# PCB_MAIN.net
KiCad netlist of a schematic drawn in EAGLE
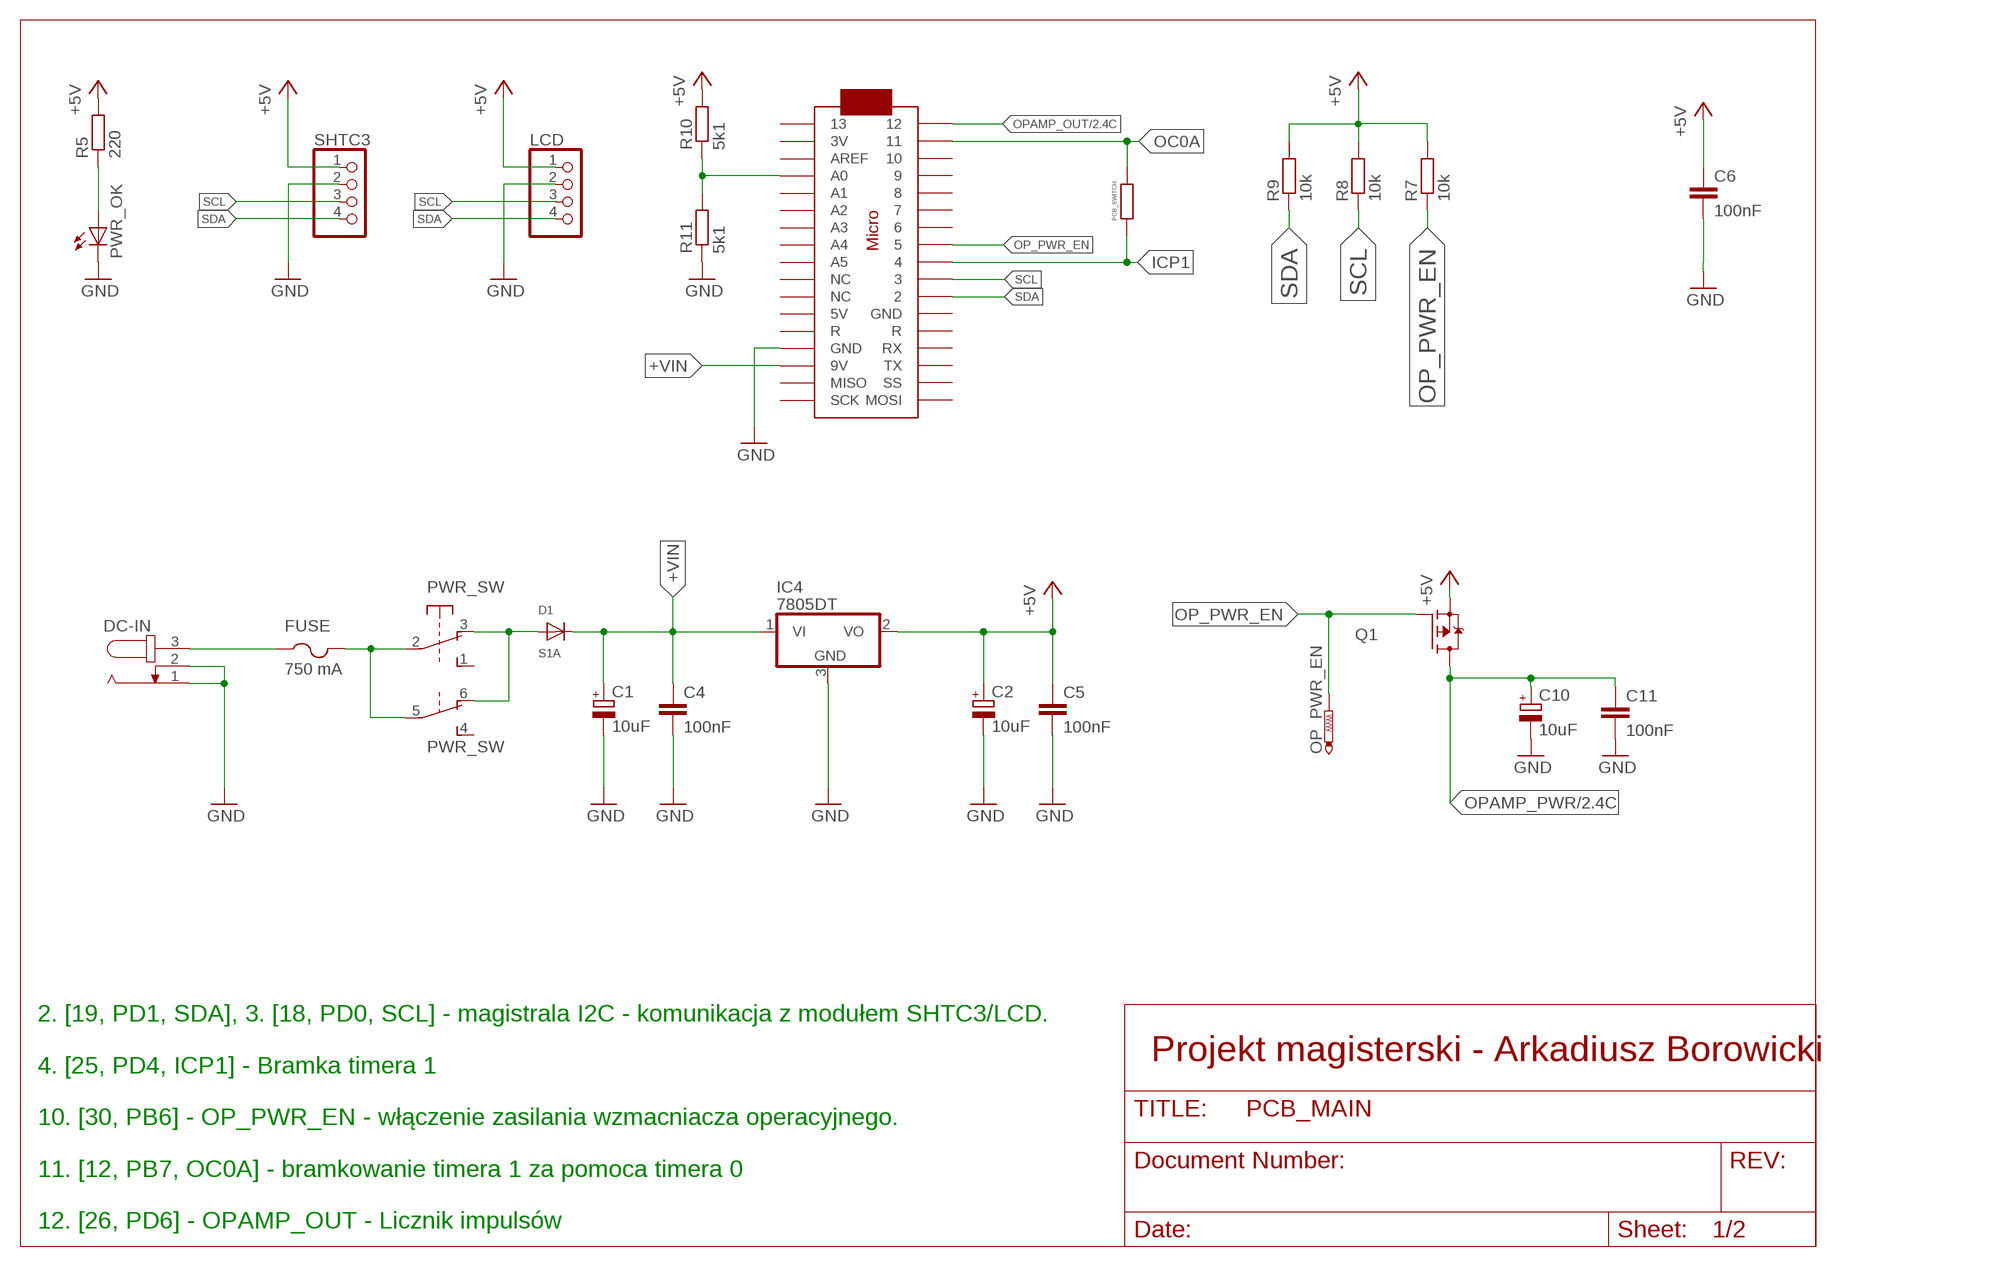
[diagram p0: schematic, sheet 1]
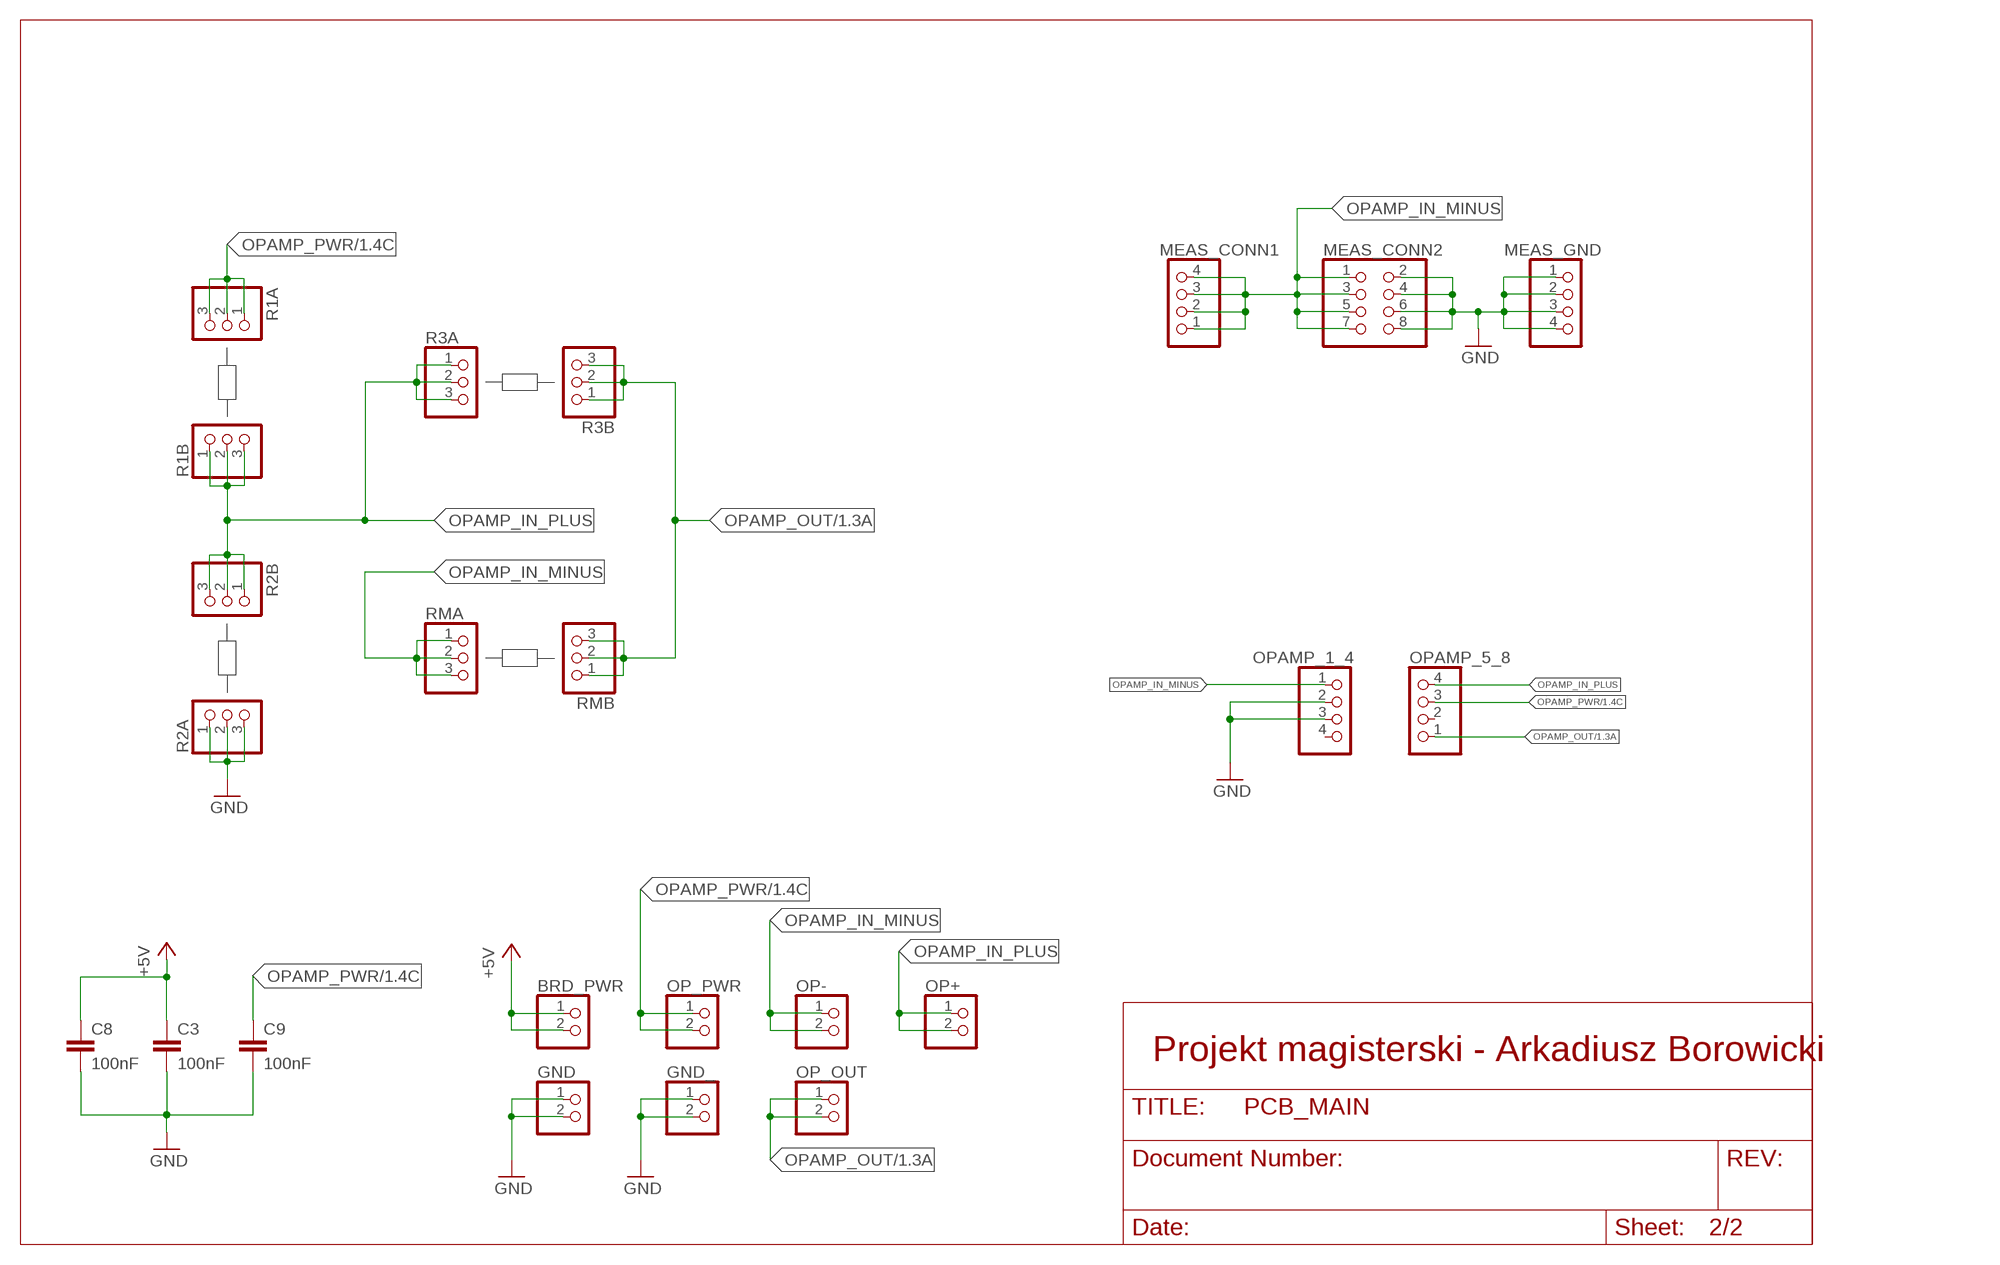
[diagram p1: schematic, sheet 2]

(export (version "E")
  (design (tool "Eeschema 10.0.6"))
  (components
    (comp (ref "BRD_PWR")
      (value "PINHD-1X2")
      (footprint "eagle-import:1X02")
      (libsource (lib "eagle-import") (part "PINHD-1X2"))
    )
    (comp (ref "C3")
      (value "100nF")
      (footprint "eagle-import:C1206K")
      (libsource (lib "eagle-import") (part "C-EUC1206K"))
    )
    (comp (ref "C8")
      (value "100nF")
      (footprint "eagle-import:C1206K")
      (libsource (lib "eagle-import") (part "C-EUC1206K"))
    )
    (comp (ref "C9")
      (value "100nF")
      (footprint "eagle-import:C1206K")
      (libsource (lib "eagle-import") (part "C-EUC1206K"))
    )
    (comp (ref "GND")
      (value "PINHD-1X2")
      (footprint "eagle-import:1X02")
      (libsource (lib "eagle-import") (part "PINHD-1X2"))
    )
    (comp (ref "GND_")
      (value "PINHD-1X2")
      (footprint "eagle-import:1X02")
      (libsource (lib "eagle-import") (part "PINHD-1X2"))
    )
    (comp (ref "MEAS_CONN1")
      (value "PINHD-1X4")
      (footprint "eagle-import:1X04")
      (libsource (lib "eagle-import") (part "PINHD-1X4"))
    )
    (comp (ref "MEAS_CONN2")
      (value "PINHD-2X4")
      (footprint "eagle-import:2X04")
      (libsource (lib "eagle-import") (part "PINHD-2X4"))
    )
    (comp (ref "MEAS_GND")
      (value "PINHD-1X4")
      (footprint "eagle-import:1X04")
      (libsource (lib "eagle-import") (part "PINHD-1X4"))
    )
    (comp (ref "OP+")
      (value "PINHD-1X2")
      (footprint "eagle-import:1X02")
      (libsource (lib "eagle-import") (part "PINHD-1X2"))
    )
    (comp (ref "OP-")
      (value "PINHD-1X2")
      (footprint "eagle-import:1X02")
      (libsource (lib "eagle-import") (part "PINHD-1X2"))
    )
    (comp (ref "OPAMP_1_4")
      (value "PINHD-1X4")
      (footprint "eagle-import:1X04")
      (libsource (lib "eagle-import") (part "PINHD-1X4"))
    )
    (comp (ref "OPAMP_5_8")
      (value "PINHD-1X4")
      (footprint "eagle-import:1X04")
      (libsource (lib "eagle-import") (part "PINHD-1X4"))
    )
    (comp (ref "OP_OUT")
      (value "PINHD-1X2")
      (footprint "eagle-import:1X02")
      (libsource (lib "eagle-import") (part "PINHD-1X2"))
    )
    (comp (ref "OP_PWR")
      (value "PINHD-1X2")
      (footprint "eagle-import:1X02")
      (libsource (lib "eagle-import") (part "PINHD-1X2"))
    )
    (comp (ref "R1A")
      (value "PINHD-1X3")
      (footprint "eagle-import:1X03")
      (libsource (lib "eagle-import") (part "PINHD-1X3"))
    )
    (comp (ref "R1B")
      (value "PINHD-1X3")
      (footprint "eagle-import:1X03")
      (libsource (lib "eagle-import") (part "PINHD-1X3"))
    )
    (comp (ref "R2A")
      (value "PINHD-1X3")
      (footprint "eagle-import:1X03")
      (libsource (lib "eagle-import") (part "PINHD-1X3"))
    )
    (comp (ref "R2B")
      (value "PINHD-1X3")
      (footprint "eagle-import:1X03")
      (libsource (lib "eagle-import") (part "PINHD-1X3"))
    )
    (comp (ref "R3A")
      (value "PINHD-1X3")
      (footprint "eagle-import:1X03")
      (libsource (lib "eagle-import") (part "PINHD-1X3"))
    )
    (comp (ref "R3B")
      (value "PINHD-1X3")
      (footprint "eagle-import:1X03")
      (libsource (lib "eagle-import") (part "PINHD-1X3"))
    )
    (comp (ref "RMA")
      (value "PINHD-1X3")
      (footprint "eagle-import:1X03")
      (libsource (lib "eagle-import") (part "PINHD-1X3"))
    )
    (comp (ref "RMB")
      (value "PINHD-1X3")
      (footprint "eagle-import:1X03")
      (libsource (lib "eagle-import") (part "PINHD-1X3"))
    )
    (comp (ref "C1")
      (value "10uF")
      (footprint "eagle-import:153CLV-0605")
      (libsource (lib "eagle-import") (part "CPOL-EU153CLV-0605"))
    )
    (comp (ref "C2")
      (value "10uF")
      (footprint "eagle-import:153CLV-0605")
      (libsource (lib "eagle-import") (part "CPOL-EU153CLV-0605"))
    )
    (comp (ref "C4")
      (value "100nF")
      (footprint "eagle-import:C1206K")
      (libsource (lib "eagle-import") (part "C-EUC1206K"))
    )
    (comp (ref "C5")
      (value "100nF")
      (footprint "eagle-import:C1206K")
      (libsource (lib "eagle-import") (part "C-EUC1206K"))
    )
    (comp (ref "C6")
      (value "100nF")
      (footprint "eagle-import:C1206K")
      (libsource (lib "eagle-import") (part "C-EUC1206K"))
    )
    (comp (ref "C10")
      (value "10uF")
      (footprint "eagle-import:153CLV-0605")
      (libsource (lib "eagle-import") (part "CPOL-EU153CLV-0605"))
    )
    (comp (ref "C11")
      (value "100nF")
      (footprint "eagle-import:C1206K")
      (libsource (lib "eagle-import") (part "C-EUC1206K"))
    )
    (comp (ref "D1")
      (value "S1A")
      (footprint "eagle-import:SMADIODE")
      (libsource (lib "eagle-import") (part "DIODESMA"))
    )
    (comp (ref "DC-IN")
      (value "JACK-PLUG1")
      (footprint "eagle-import:SPC4078")
      (libsource (lib "eagle-import") (part "JACK-PLUG1"))
    )
    (comp (ref "FUSE")
      (value "750 mA")
      (footprint "eagle-import:1812")
      (libsource (lib "eagle-import") (part "PTCFUSE-1812"))
    )
    (comp (ref "IC4")
      (value "7805DT")
      (footprint "eagle-import:TO252")
      (libsource (lib "eagle-import") (part "78DT05"))
    )
    (comp (ref "LCD")
      (value "PINHD-1X4")
      (footprint "eagle-import:1X04")
      (libsource (lib "eagle-import") (part "PINHD-1X4"))
    )
    (comp (ref "OP_PWR_EN")
      (value "PTR1TP20R")
      (footprint "eagle-import:TP20R")
      (libsource (lib "eagle-import") (part "PTR1TP20R"))
    )
    (comp (ref "PCB_SWITCH")
      (value "R-EU_R0402")
      (footprint "eagle-import:R0402")
      (libsource (lib "eagle-import") (part "resistor_348_R-EU_R0402"))
    )
    (comp (ref "PWR_OK")
      (value "LEDSMT1206")
      (footprint "eagle-import:1206")
      (libsource (lib "eagle-import") (part "LEDSMT1206"))
    )
    (comp (ref "PWR_SW")
      (value "9077-2")
      (footprint "eagle-import:9077-2")
      (libsource (lib "eagle-import") (part "9077-2"))
    )
    (comp (ref "Q1")
      (value "SPD30P06PTO252")
      (footprint "eagle-import:TO252")
      (libsource (lib "eagle-import") (part "SPD30P06PTO252"))
    )
    (comp (ref "R5")
      (value "220")
      (footprint "eagle-import:R1206")
      (libsource (lib "eagle-import") (part "R-EU_R1206"))
    )
    (comp (ref "R7")
      (value "10k")
      (footprint "eagle-import:R1206")
      (libsource (lib "eagle-import") (part "R-EU_R1206"))
    )
    (comp (ref "R8")
      (value "10k")
      (footprint "eagle-import:R1206")
      (libsource (lib "eagle-import") (part "R-EU_R1206"))
    )
    (comp (ref "R9")
      (value "10k")
      (footprint "eagle-import:R1206")
      (libsource (lib "eagle-import") (part "R-EU_R1206"))
    )
    (comp (ref "R10")
      (value "5k1")
      (footprint "eagle-import:R1206")
      (libsource (lib "eagle-import") (part "R-EU_R1206"))
    )
    (comp (ref "R11")
      (value "5k1")
      (footprint "eagle-import:R1206")
      (libsource (lib "eagle-import") (part "R-EU_R1206"))
    )
    (comp (ref "SHTC3")
      (value "PINHD-1X4")
      (footprint "eagle-import:1X04")
      (libsource (lib "eagle-import") (part "PINHD-1X4"))
    )
    (comp (ref "U$1")
      (value "ARDUINOMICRO")
      (footprint "eagle-import:ARDUINOMICRO")
      (libsource (lib "eagle-import") (part "ARDUINOMICRO"))
    )
  )
  (nets
    (net (code "1") (name "+5V") (class "Default")
      (node (ref "BRD_PWR") (pin "1") (pinfunction "1_1") (pintype "passive"))
      (node (ref "BRD_PWR") (pin "2") (pinfunction "2_2") (pintype "passive"))
      (node (ref "C2") (pin "+") (pinfunction "+_+") (pintype "passive"))
      (node (ref "C3") (pin "1") (pinfunction "1_1") (pintype "passive"))
      (node (ref "C5") (pin "1") (pinfunction "1_1") (pintype "passive"))
      (node (ref "C6") (pin "1") (pinfunction "1_1") (pintype "passive"))
      (node (ref "C8") (pin "1") (pinfunction "1_1") (pintype "passive"))
      (node (ref "IC4") (pin "2") (pinfunction "VO_2") (pintype "passive"))
      (node (ref "LCD") (pin "1") (pinfunction "1_1") (pintype "passive"))
      (node (ref "Q1") (pin "2") (pinfunction "S_2") (pintype "passive"))
      (node (ref "R10") (pin "2") (pinfunction "2_2") (pintype "passive"))
      (node (ref "R5") (pin "2") (pinfunction "2_2") (pintype "passive"))
      (node (ref "R7") (pin "2") (pinfunction "2_2") (pintype "passive"))
      (node (ref "R8") (pin "2") (pinfunction "2_2") (pintype "passive"))
      (node (ref "R9") (pin "2") (pinfunction "2_2") (pintype "passive"))
      (node (ref "SHTC3") (pin "1") (pinfunction "1_1") (pintype "passive"))
    )
    (net (code "2") (name "+VIN") (class "Default")
      (node (ref "C1") (pin "+") (pinfunction "+_+") (pintype "passive"))
      (node (ref "C4") (pin "1") (pinfunction "1_1") (pintype "passive"))
      (node (ref "D1") (pin "C") (pinfunction "C_C") (pintype "passive"))
      (node (ref "IC4") (pin "1") (pinfunction "VI_1") (pintype "input"))
      (node (ref "U$1") (pin "P$20") (pinfunction "9V_P$20") (pintype "bidirectional"))
    )
    (net (code "3") (name "GND") (class "Default")
      (node (ref "C1") (pin "-") (pinfunction "-_-") (pintype "passive"))
      (node (ref "C10") (pin "-") (pinfunction "-_-") (pintype "passive"))
      (node (ref "C11") (pin "2") (pinfunction "2_2") (pintype "passive"))
      (node (ref "C2") (pin "-") (pinfunction "-_-") (pintype "passive"))
      (node (ref "C3") (pin "2") (pinfunction "2_2") (pintype "passive"))
      (node (ref "C4") (pin "2") (pinfunction "2_2") (pintype "passive"))
      (node (ref "C5") (pin "2") (pinfunction "2_2") (pintype "passive"))
      (node (ref "C6") (pin "2") (pinfunction "2_2") (pintype "passive"))
      (node (ref "C8") (pin "2") (pinfunction "2_2") (pintype "passive"))
      (node (ref "C9") (pin "2") (pinfunction "2_2") (pintype "passive"))
      (node (ref "DC-IN") (pin "1") (pinfunction "1_1") (pintype "passive"))
      (node (ref "DC-IN") (pin "2") (pinfunction "2_2") (pintype "passive"))
      (node (ref "GND") (pin "1") (pinfunction "1_1") (pintype "passive"))
      (node (ref "GND") (pin "2") (pinfunction "2_2") (pintype "passive"))
      (node (ref "GND_") (pin "1") (pinfunction "1_1") (pintype "passive"))
      (node (ref "GND_") (pin "2") (pinfunction "2_2") (pintype "passive"))
      (node (ref "IC4") (pin "3") (pinfunction "GND_3") (pintype "passive"))
      (node (ref "LCD") (pin "2") (pinfunction "2_2") (pintype "passive"))
      (node (ref "MEAS_CONN2") (pin "2") (pinfunction "2_2") (pintype "passive"))
      (node (ref "MEAS_CONN2") (pin "4") (pinfunction "4_4") (pintype "passive"))
      (node (ref "MEAS_CONN2") (pin "6") (pinfunction "6_6") (pintype "passive"))
      (node (ref "MEAS_CONN2") (pin "8") (pinfunction "8_8") (pintype "passive"))
      (node (ref "MEAS_GND") (pin "1") (pinfunction "1_1") (pintype "passive"))
      (node (ref "MEAS_GND") (pin "2") (pinfunction "2_2") (pintype "passive"))
      (node (ref "MEAS_GND") (pin "3") (pinfunction "3_3") (pintype "passive"))
      (node (ref "MEAS_GND") (pin "4") (pinfunction "4_4") (pintype "passive"))
      (node (ref "OPAMP_1_4") (pin "2") (pinfunction "2_2") (pintype "passive"))
      (node (ref "OPAMP_1_4") (pin "3") (pinfunction "3_3") (pintype "passive"))
      (node (ref "PWR_OK") (pin "C") (pinfunction "C_C") (pintype "passive"))
      (node (ref "R11") (pin "1") (pinfunction "1_1") (pintype "passive"))
      (node (ref "R2A") (pin "1") (pinfunction "1_1") (pintype "passive"))
      (node (ref "R2A") (pin "2") (pinfunction "2_2") (pintype "passive"))
      (node (ref "R2A") (pin "3") (pinfunction "3_3") (pintype "passive"))
      (node (ref "SHTC3") (pin "2") (pinfunction "2_2") (pintype "passive"))
      (node (ref "U$1") (pin "P$12") (pinfunction "GND_P$12") (pintype "bidirectional"))
    )
    (net (code "4") (name "ICP1") (class "Default")
      (node (ref "PCB_SWITCH") (pin "1") (pinfunction "1_1") (pintype "passive"))
      (node (ref "U$1") (pin "P$9") (pinfunction "4_P$9") (pintype "bidirectional"))
    )
    (net (code "5") (name "Net-(DC-IN-Pad3)") (class "Default")
      (node (ref "DC-IN") (pin "3") (pinfunction "3_3") (pintype "passive"))
      (node (ref "FUSE") (pin "1") (pinfunction "1_1") (pintype "passive"))
    )
    (net (code "6") (name "Net-(PWR_OK-PadA)") (class "Default")
      (node (ref "PWR_OK") (pin "A") (pinfunction "A_A") (pintype "passive"))
      (node (ref "R5") (pin "1") (pinfunction "1_1") (pintype "passive"))
    )
    (net (code "7") (name "Net-(PWR_SWA-O)") (class "Default")
      (node (ref "D1") (pin "A") (pinfunction "A_A") (pintype "passive"))
      (node (ref "PWR_SW") (pin "3") (pinfunction "O_3") (pintype "passive"))
      (node (ref "PWR_SW") (pin "6") (pinfunction "O_6") (pintype "passive"))
    )
    (net (code "8") (name "Net-(PWR_SWA-P)") (class "Default")
      (node (ref "FUSE") (pin "2") (pinfunction "2_2") (pintype "passive"))
      (node (ref "PWR_SW") (pin "2") (pinfunction "P_2") (pintype "passive"))
      (node (ref "PWR_SW") (pin "5") (pinfunction "P_5") (pintype "passive"))
    )
    (net (code "9") (name "Net-(U$1-A0)") (class "Default")
      (node (ref "R10") (pin "1") (pinfunction "1_1") (pintype "passive"))
      (node (ref "R11") (pin "2") (pinfunction "2_2") (pintype "passive"))
      (node (ref "U$1") (pin "P$31") (pinfunction "A0_P$31") (pintype "bidirectional"))
    )
    (net (code "10") (name "OC0A") (class "Default")
      (node (ref "PCB_SWITCH") (pin "2") (pinfunction "2_2") (pintype "passive"))
      (node (ref "U$1") (pin "P$2") (pinfunction "11_P$2") (pintype "bidirectional"))
    )
    (net (code "11") (name "OPAMP_IN_MINUS") (class "Default")
      (node (ref "MEAS_CONN1") (pin "1") (pinfunction "1_1") (pintype "passive"))
      (node (ref "MEAS_CONN1") (pin "2") (pinfunction "2_2") (pintype "passive"))
      (node (ref "MEAS_CONN1") (pin "3") (pinfunction "3_3") (pintype "passive"))
      (node (ref "MEAS_CONN1") (pin "4") (pinfunction "4_4") (pintype "passive"))
      (node (ref "MEAS_CONN2") (pin "1") (pinfunction "1_1") (pintype "passive"))
      (node (ref "MEAS_CONN2") (pin "3") (pinfunction "3_3") (pintype "passive"))
      (node (ref "MEAS_CONN2") (pin "5") (pinfunction "5_5") (pintype "passive"))
      (node (ref "MEAS_CONN2") (pin "7") (pinfunction "7_7") (pintype "passive"))
      (node (ref "OP-") (pin "1") (pinfunction "1_1") (pintype "passive"))
      (node (ref "OP-") (pin "2") (pinfunction "2_2") (pintype "passive"))
      (node (ref "OPAMP_1_4") (pin "1") (pinfunction "1_1") (pintype "passive"))
      (node (ref "RMA") (pin "1") (pinfunction "1_1") (pintype "passive"))
      (node (ref "RMA") (pin "2") (pinfunction "2_2") (pintype "passive"))
      (node (ref "RMA") (pin "3") (pinfunction "3_3") (pintype "passive"))
    )
    (net (code "12") (name "OPAMP_IN_PLUS") (class "Default")
      (node (ref "OP+") (pin "1") (pinfunction "1_1") (pintype "passive"))
      (node (ref "OP+") (pin "2") (pinfunction "2_2") (pintype "passive"))
      (node (ref "OPAMP_5_8") (pin "4") (pinfunction "4_4") (pintype "passive"))
      (node (ref "R1B") (pin "1") (pinfunction "1_1") (pintype "passive"))
      (node (ref "R1B") (pin "2") (pinfunction "2_2") (pintype "passive"))
      (node (ref "R1B") (pin "3") (pinfunction "3_3") (pintype "passive"))
      (node (ref "R2B") (pin "1") (pinfunction "1_1") (pintype "passive"))
      (node (ref "R2B") (pin "2") (pinfunction "2_2") (pintype "passive"))
      (node (ref "R2B") (pin "3") (pinfunction "3_3") (pintype "passive"))
      (node (ref "R3A") (pin "1") (pinfunction "1_1") (pintype "passive"))
      (node (ref "R3A") (pin "2") (pinfunction "2_2") (pintype "passive"))
      (node (ref "R3A") (pin "3") (pinfunction "3_3") (pintype "passive"))
    )
    (net (code "13") (name "OPAMP_OUT") (class "Default")
      (node (ref "OPAMP_5_8") (pin "1") (pinfunction "1_1") (pintype "passive"))
      (node (ref "OP_OUT") (pin "1") (pinfunction "1_1") (pintype "passive"))
      (node (ref "OP_OUT") (pin "2") (pinfunction "2_2") (pintype "passive"))
      (node (ref "R3B") (pin "1") (pinfunction "1_1") (pintype "passive"))
      (node (ref "R3B") (pin "2") (pinfunction "2_2") (pintype "passive"))
      (node (ref "R3B") (pin "3") (pinfunction "3_3") (pintype "passive"))
      (node (ref "RMB") (pin "1") (pinfunction "1_1") (pintype "passive"))
      (node (ref "RMB") (pin "2") (pinfunction "2_2") (pintype "passive"))
      (node (ref "RMB") (pin "3") (pinfunction "3_3") (pintype "passive"))
      (node (ref "U$1") (pin "P$1") (pinfunction "12_P$1") (pintype "bidirectional"))
    )
    (net (code "14") (name "OPAMP_PWR") (class "Default")
      (node (ref "C10") (pin "+") (pinfunction "+_+") (pintype "passive"))
      (node (ref "C11") (pin "1") (pinfunction "1_1") (pintype "passive"))
      (node (ref "C9") (pin "1") (pinfunction "1_1") (pintype "passive"))
      (node (ref "OPAMP_5_8") (pin "3") (pinfunction "3_3") (pintype "passive"))
      (node (ref "OP_PWR") (pin "1") (pinfunction "1_1") (pintype "passive"))
      (node (ref "OP_PWR") (pin "2") (pinfunction "2_2") (pintype "passive"))
      (node (ref "Q1") (pin "3") (pinfunction "D_3") (pintype "passive"))
      (node (ref "R1A") (pin "1") (pinfunction "1_1") (pintype "passive"))
      (node (ref "R1A") (pin "2") (pinfunction "2_2") (pintype "passive"))
      (node (ref "R1A") (pin "3") (pinfunction "3_3") (pintype "passive"))
    )
    (net (code "15") (name "OP_PWR_EN") (class "Default")
      (node (ref "OP_PWR_EN") (pin "TP") (pinfunction "TP_TP") (pintype "input"))
      (node (ref "Q1") (pin "1") (pinfunction "G_1") (pintype "passive"))
      (node (ref "R7") (pin "1") (pinfunction "1_1") (pintype "passive"))
      (node (ref "U$1") (pin "P$8") (pinfunction "5_P$8") (pintype "bidirectional"))
    )
    (net (code "16") (name "SCL") (class "Default")
      (node (ref "LCD") (pin "3") (pinfunction "3_3") (pintype "passive"))
      (node (ref "R8") (pin "1") (pinfunction "1_1") (pintype "passive"))
      (node (ref "SHTC3") (pin "3") (pinfunction "3_3") (pintype "passive"))
      (node (ref "U$1") (pin "P$10") (pinfunction "3_P$10") (pintype "bidirectional"))
    )
    (net (code "17") (name "SDA") (class "Default")
      (node (ref "LCD") (pin "4") (pinfunction "4_4") (pintype "passive"))
      (node (ref "R9") (pin "1") (pinfunction "1_1") (pintype "passive"))
      (node (ref "SHTC3") (pin "4") (pinfunction "4_4") (pintype "passive"))
      (node (ref "U$1") (pin "P$11") (pinfunction "2_P$11") (pintype "bidirectional"))
    )
    (net (code "18") (name "unconnected-(OPAMP_1_4-Pad4)") (class "Default")
      (node (ref "OPAMP_1_4") (pin "4") (pinfunction "4_4") (pintype "passive"))
    )
    (net (code "19") (name "unconnected-(OPAMP_5_8-Pad2)") (class "Default")
      (node (ref "OPAMP_5_8") (pin "2") (pinfunction "2_2") (pintype "passive"))
    )
    (net (code "20") (name "unconnected-(PWR_SWA-S-Pad1)") (class "Default")
      (node (ref "PWR_SW") (pin "1") (pinfunction "S_1") (pintype "passive"))
    )
    (net (code "21") (name "unconnected-(PWR_SWB-S-Pad4)") (class "Default")
      (node (ref "PWR_SW") (pin "4") (pinfunction "S_4") (pintype "passive"))
    )
    (net (code "22") (name "unconnected-(U$1-3V-PadP$33)") (class "Default")
      (node (ref "U$1") (pin "P$33") (pinfunction "3V_P$33") (pintype "bidirectional"))
    )
    (net (code "23") (name "unconnected-(U$1-5V-PadP$23)") (class "Default")
      (node (ref "U$1") (pin "P$23") (pinfunction "5V_P$23") (pintype "bidirectional"))
    )
    (net (code "24") (name "unconnected-(U$1-6-PadP$7)") (class "Default")
      (node (ref "U$1") (pin "P$7") (pinfunction "6_P$7") (pintype "bidirectional"))
    )
    (net (code "25") (name "unconnected-(U$1-7-PadP$6)") (class "Default")
      (node (ref "U$1") (pin "P$6") (pinfunction "7_P$6") (pintype "bidirectional"))
    )
    (net (code "26") (name "unconnected-(U$1-8-PadP$5)") (class "Default")
      (node (ref "U$1") (pin "P$5") (pinfunction "8_P$5") (pintype "bidirectional"))
    )
    (net (code "27") (name "unconnected-(U$1-9-PadP$4)") (class "Default")
      (node (ref "U$1") (pin "P$4") (pinfunction "9_P$4") (pintype "bidirectional"))
    )
    (net (code "28") (name "unconnected-(U$1-10-PadP$3)") (class "Default")
      (node (ref "U$1") (pin "P$3") (pinfunction "10_P$3") (pintype "bidirectional"))
    )
    (net (code "29") (name "unconnected-(U$1-13-PadP$34)") (class "Default")
      (node (ref "U$1") (pin "P$34") (pinfunction "13_P$34") (pintype "bidirectional"))
    )
    (net (code "30") (name "unconnected-(U$1-A1-PadP$30)") (class "Default")
      (node (ref "U$1") (pin "P$30") (pinfunction "A1_P$30") (pintype "bidirectional"))
    )
    (net (code "31") (name "unconnected-(U$1-A2-PadP$29)") (class "Default")
      (node (ref "U$1") (pin "P$29") (pinfunction "A2_P$29") (pintype "bidirectional"))
    )
    (net (code "32") (name "unconnected-(U$1-A3-PadP$28)") (class "Default")
      (node (ref "U$1") (pin "P$28") (pinfunction "A3_P$28") (pintype "bidirectional"))
    )
    (net (code "33") (name "unconnected-(U$1-A4-PadP$27)") (class "Default")
      (node (ref "U$1") (pin "P$27") (pinfunction "A4_P$27") (pintype "bidirectional"))
    )
    (net (code "34") (name "unconnected-(U$1-A5-PadP$26)") (class "Default")
      (node (ref "U$1") (pin "P$26") (pinfunction "A5_P$26") (pintype "bidirectional"))
    )
    (net (code "35") (name "unconnected-(U$1-AREF-PadP$32)") (class "Default")
      (node (ref "U$1") (pin "P$32") (pinfunction "AREF_P$32") (pintype "bidirectional"))
    )
    (net (code "36") (name "unconnected-(U$1-GND-PadP$21)") (class "Default")
      (node (ref "U$1") (pin "P$21") (pinfunction "GND_P$21") (pintype "bidirectional"))
    )
    (net (code "37") (name "unconnected-(U$1-MISO-PadP$19)") (class "Default")
      (node (ref "U$1") (pin "P$19") (pinfunction "MISO_P$19") (pintype "bidirectional"))
    )
    (net (code "38") (name "unconnected-(U$1-MOSI-PadP$17)") (class "Default")
      (node (ref "U$1") (pin "P$17") (pinfunction "MOSI_P$17") (pintype "bidirectional"))
    )
    (net (code "39") (name "unconnected-(U$1-NC-PadP$24)") (class "Default")
      (node (ref "U$1") (pin "P$24") (pinfunction "NC_P$24") (pintype "bidirectional"))
    )
    (net (code "40") (name "unconnected-(U$1-NC-PadP$25)") (class "Default")
      (node (ref "U$1") (pin "P$25") (pinfunction "NC_P$25") (pintype "bidirectional"))
    )
    (net (code "41") (name "unconnected-(U$1-R-PadP$13)") (class "Default")
      (node (ref "U$1") (pin "P$13") (pinfunction "R_P$13") (pintype "bidirectional"))
    )
    (net (code "42") (name "unconnected-(U$1-R-PadP$22)") (class "Default")
      (node (ref "U$1") (pin "P$22") (pinfunction "R_P$22") (pintype "bidirectional"))
    )
    (net (code "43") (name "unconnected-(U$1-RX-PadP$14)") (class "Default")
      (node (ref "U$1") (pin "P$14") (pinfunction "RX_P$14") (pintype "bidirectional"))
    )
    (net (code "44") (name "unconnected-(U$1-SCK-PadP$18)") (class "Default")
      (node (ref "U$1") (pin "P$18") (pinfunction "SCK_P$18") (pintype "bidirectional"))
    )
    (net (code "45") (name "unconnected-(U$1-SS-PadP$16)") (class "Default")
      (node (ref "U$1") (pin "P$16") (pinfunction "SS_P$16") (pintype "bidirectional"))
    )
    (net (code "46") (name "unconnected-(U$1-TX-PadP$15)") (class "Default")
      (node (ref "U$1") (pin "P$15") (pinfunction "TX_P$15") (pintype "bidirectional"))
    )
  )
)
